# SCH_NFC-PCB-Business-Card-v3.net
KiCad netlist of a schematic drawn in EasyEDA
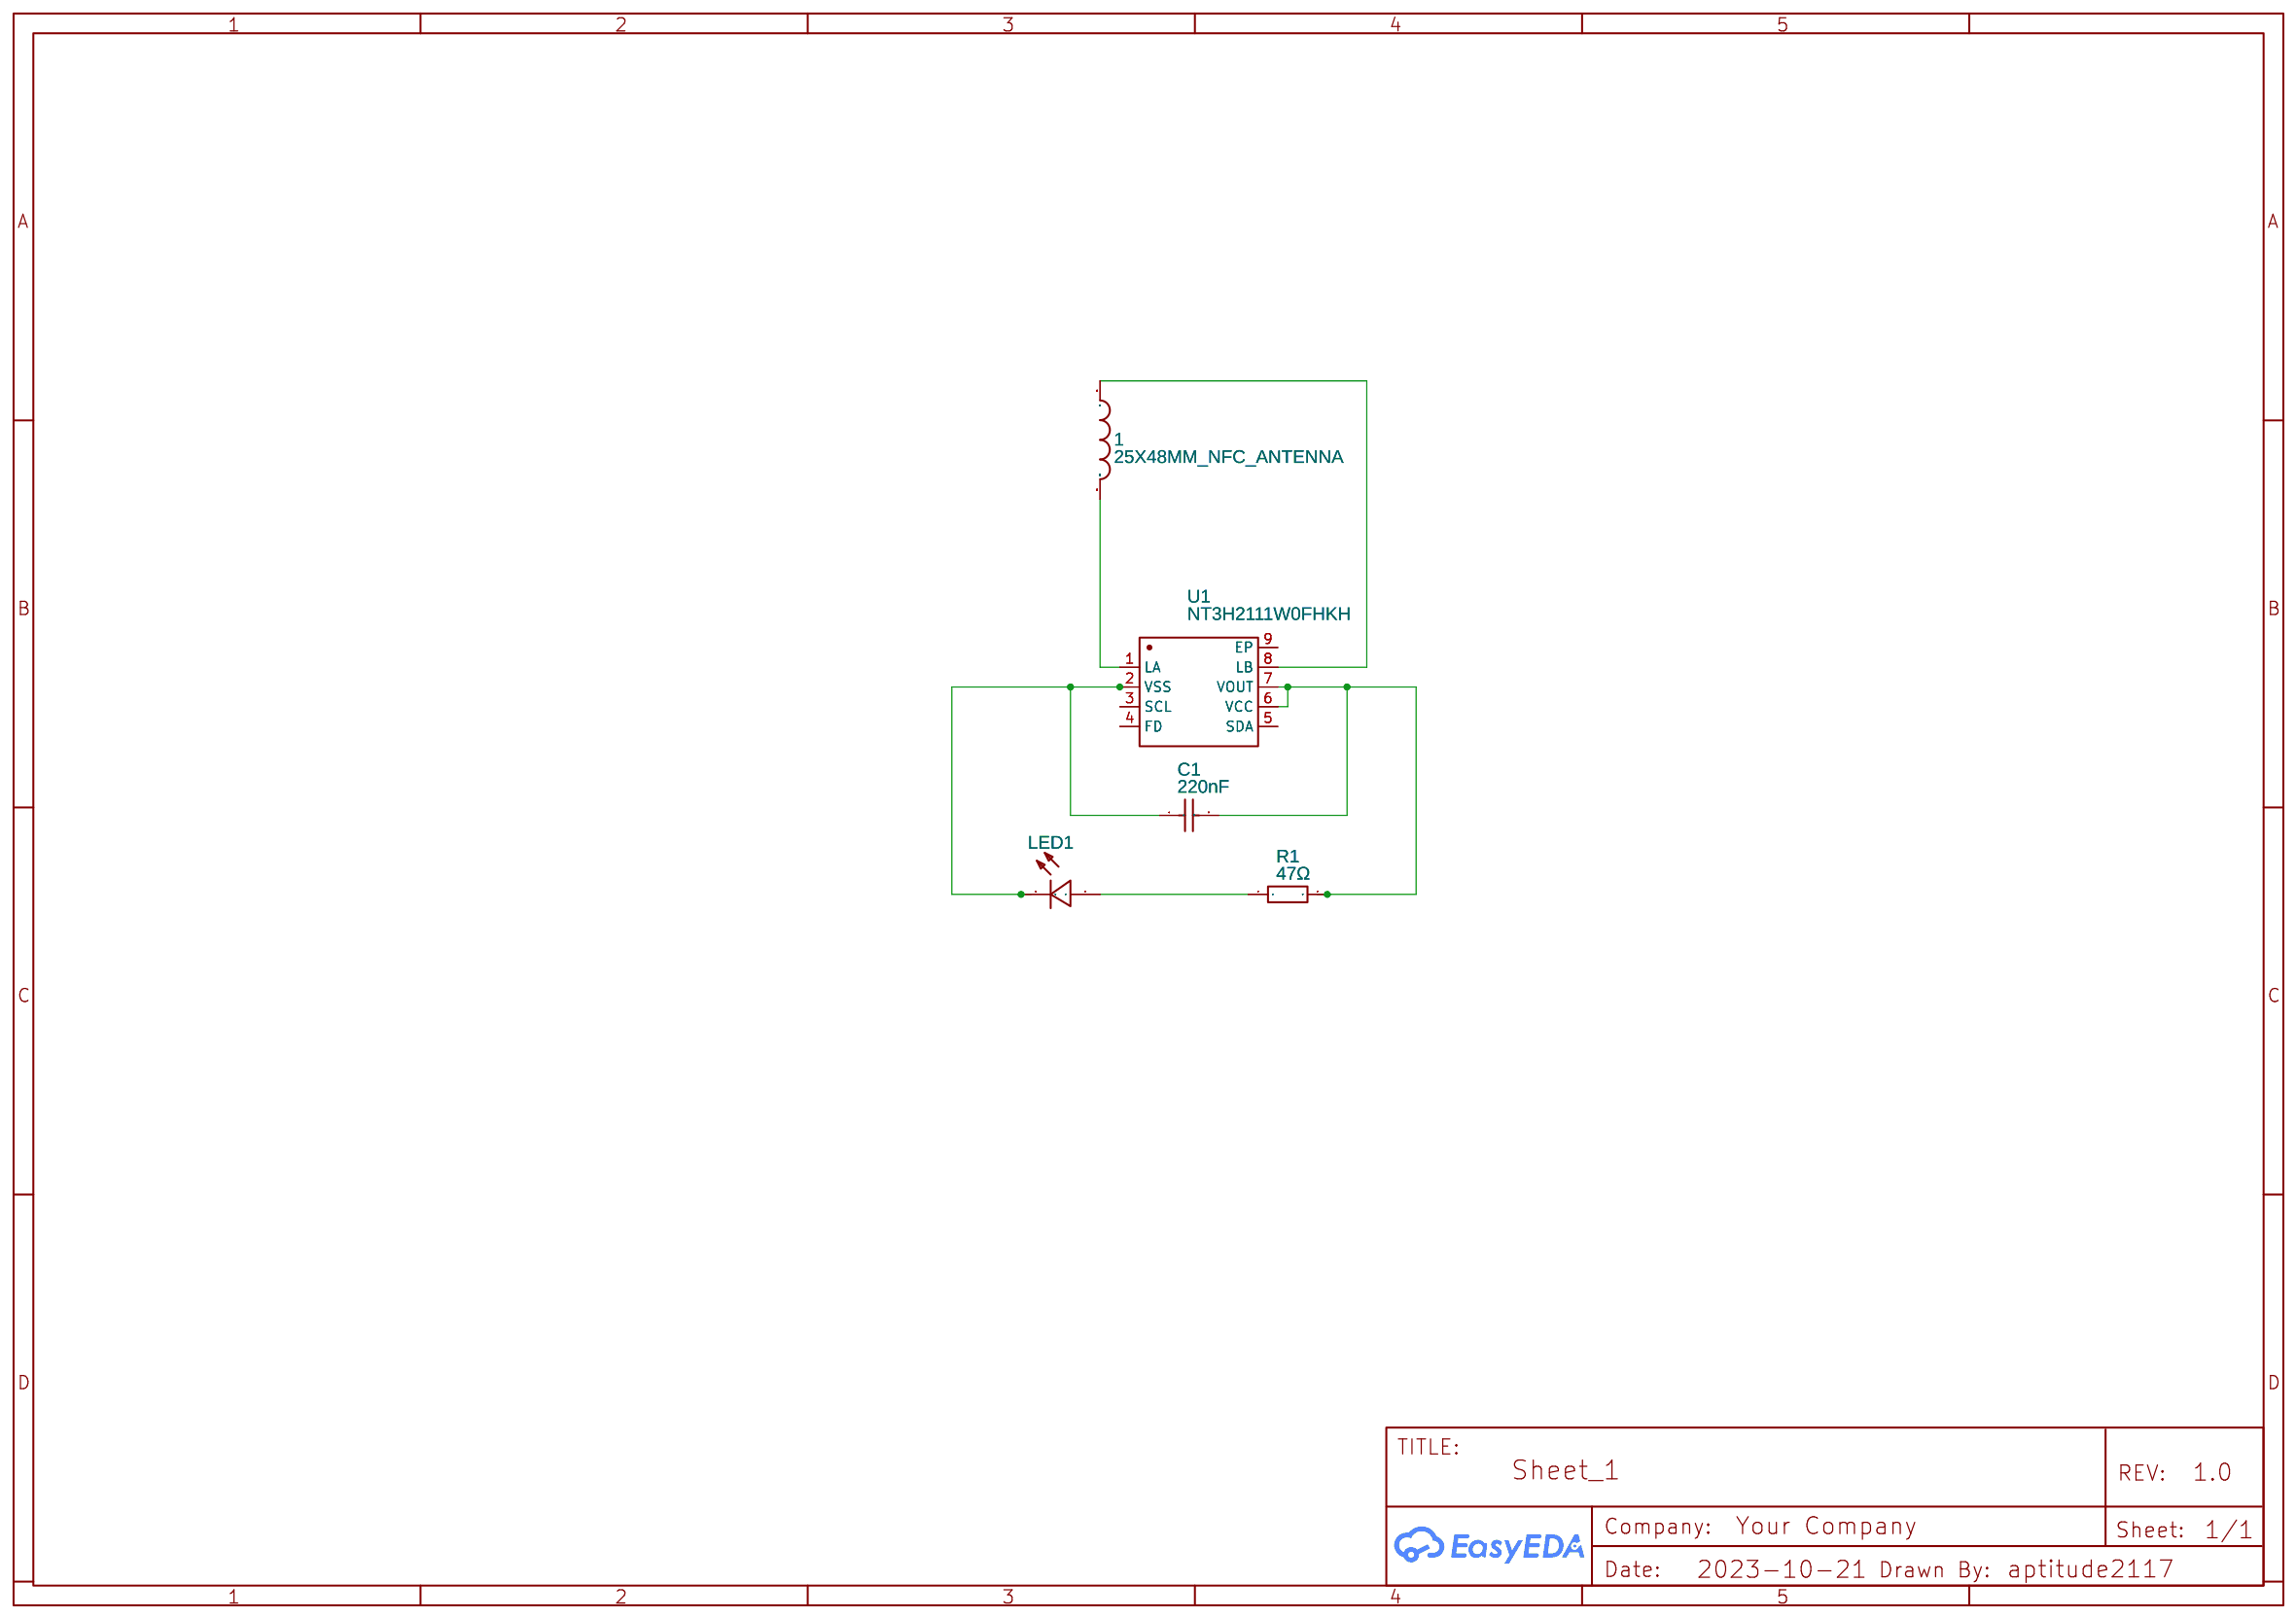
[diagram p0: schematic sheet]

(export (version "E")
  (design (tool "Eeschema 10.0.6"))
  (components
    (comp (ref "1") (value "25X48MM_NFC_ANTENNA") (libsource (lib "") (part "25X48MM_NFC_ANTENNA")))
    (comp (ref "C1")
      (value "220nF")
      (fields
        (field (name "Manufacturer Part") "CL10B224KA8NNNC")
        (field (name "Manufacturer") "SAMSUNG(三星)")
      )
      (libsource (lib "") (part "CL10B224KA8NNNC"))
    )
    (comp (ref "LED1")
      (value "17-21UYOC/S530-A2/TR8")
      (fields (field (name "Manufacturer") "EVERLIGHT(亿光)"))
      (libsource (lib "") (part "17-21UYOC/S530-A2/TR8"))
    )
    (comp (ref "R1")
      (value "47Ω")
      (fields
        (field (name "Manufacturer Part") "0603WAF470JT5E")
        (field (name "Manufacturer") "UNI-ROYAL(厚声)")
      )
      (libsource (lib "") (part "0603WAF470JT5E"))
    )
    (comp (ref "U1")
      (value "NT3H2111W0FHKH")
      (fields (field (name "Manufacturer") "NXP(恩智浦)"))
      (libsource (lib "") (part "NT3H2111W0FHKH"))
    )
  )
  (nets
    (net (code "1") (name "Net-(LED1-Pad1)") (class "Default")
      (node (ref "LED1") (pin "1") (pinfunction "1_1") (pintype "unspecified"))
      (node (ref "R1") (pin "1") (pinfunction "1_1") (pintype "input"))
    )
    (net (code "2") (name "Net-(U1-LA)") (class "Default")
      (node (ref "1") (pin "P$2") (pinfunction "P$2_P$2") (pintype "bidirectional"))
      (node (ref "U1") (pin "1") (pinfunction "LA_1") (pintype "unspecified"))
    )
    (net (code "3") (name "Net-(U1-LB)") (class "Default")
      (node (ref "1") (pin "P$1") (pinfunction "P$1_P$1") (pintype "bidirectional"))
      (node (ref "U1") (pin "8") (pinfunction "LB_8") (pintype "unspecified"))
    )
    (net (code "4") (name "Net-(U1-VCC)") (class "Default")
      (node (ref "C1") (pin "2") (pinfunction "2_2") (pintype "input"))
      (node (ref "R1") (pin "2") (pinfunction "2_2") (pintype "input"))
      (node (ref "U1") (pin "6") (pinfunction "VCC_6") (pintype "unspecified"))
      (node (ref "U1") (pin "7") (pinfunction "VOUT_7") (pintype "unspecified"))
    )
    (net (code "5") (name "Net-(U1-VSS)") (class "Default")
      (node (ref "C1") (pin "1") (pinfunction "1_1") (pintype "input"))
      (node (ref "LED1") (pin "2") (pinfunction "2_2") (pintype "unspecified"))
      (node (ref "U1") (pin "2") (pinfunction "VSS_2") (pintype "unspecified"))
    )
    (net (code "6") (name "unconnected-(U1-EP-Pad9)") (class "Default")
      (node (ref "U1") (pin "9") (pinfunction "EP_9") (pintype "unspecified"))
    )
    (net (code "7") (name "unconnected-(U1-FD-Pad4)") (class "Default")
      (node (ref "U1") (pin "4") (pinfunction "FD_4") (pintype "unspecified"))
    )
    (net (code "8") (name "unconnected-(U1-SCL-Pad3)") (class "Default")
      (node (ref "U1") (pin "3") (pinfunction "SCL_3") (pintype "unspecified"))
    )
    (net (code "9") (name "unconnected-(U1-SDA-Pad5)") (class "Default")
      (node (ref "U1") (pin "5") (pinfunction "SDA_5") (pintype "unspecified"))
    )
  )
)
